# SCH_5_Li_ion_battery_charger_2022-08-25.net
KiCad netlist of a schematic drawn in EasyEDA
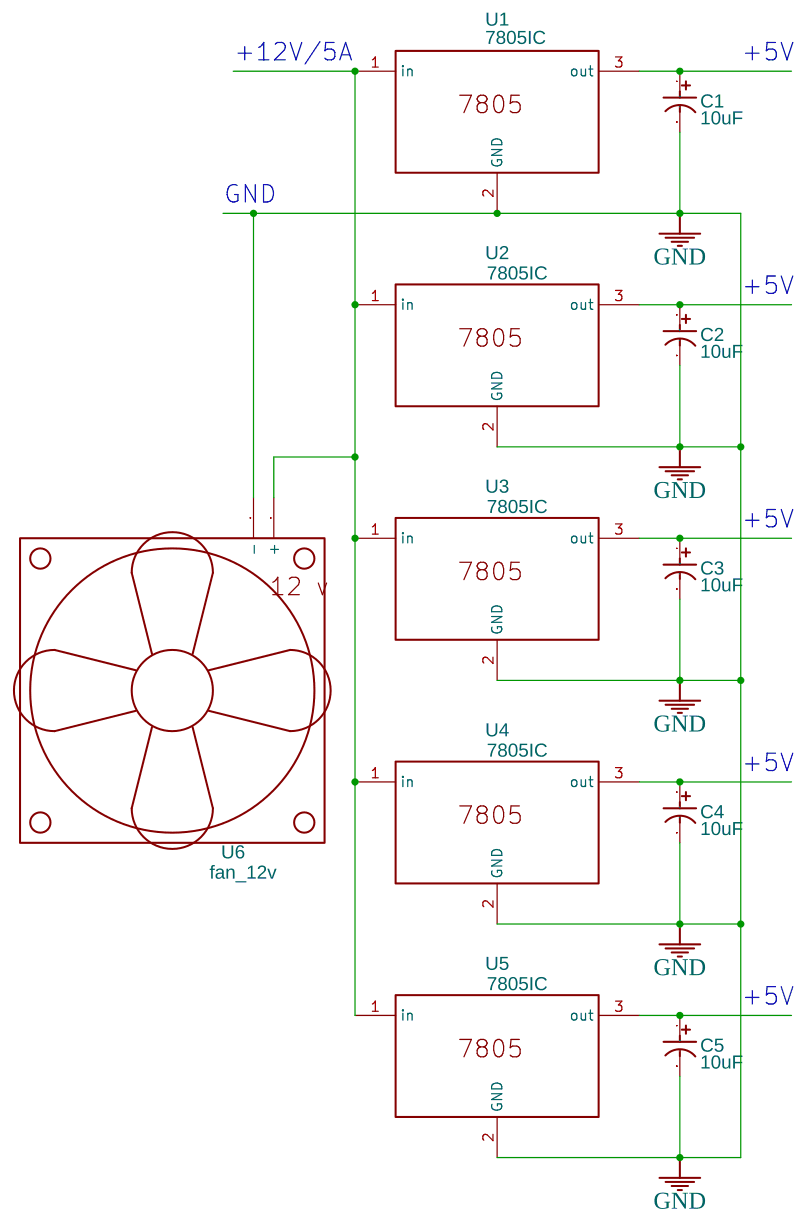
[diagram p0: 12v to 5v]
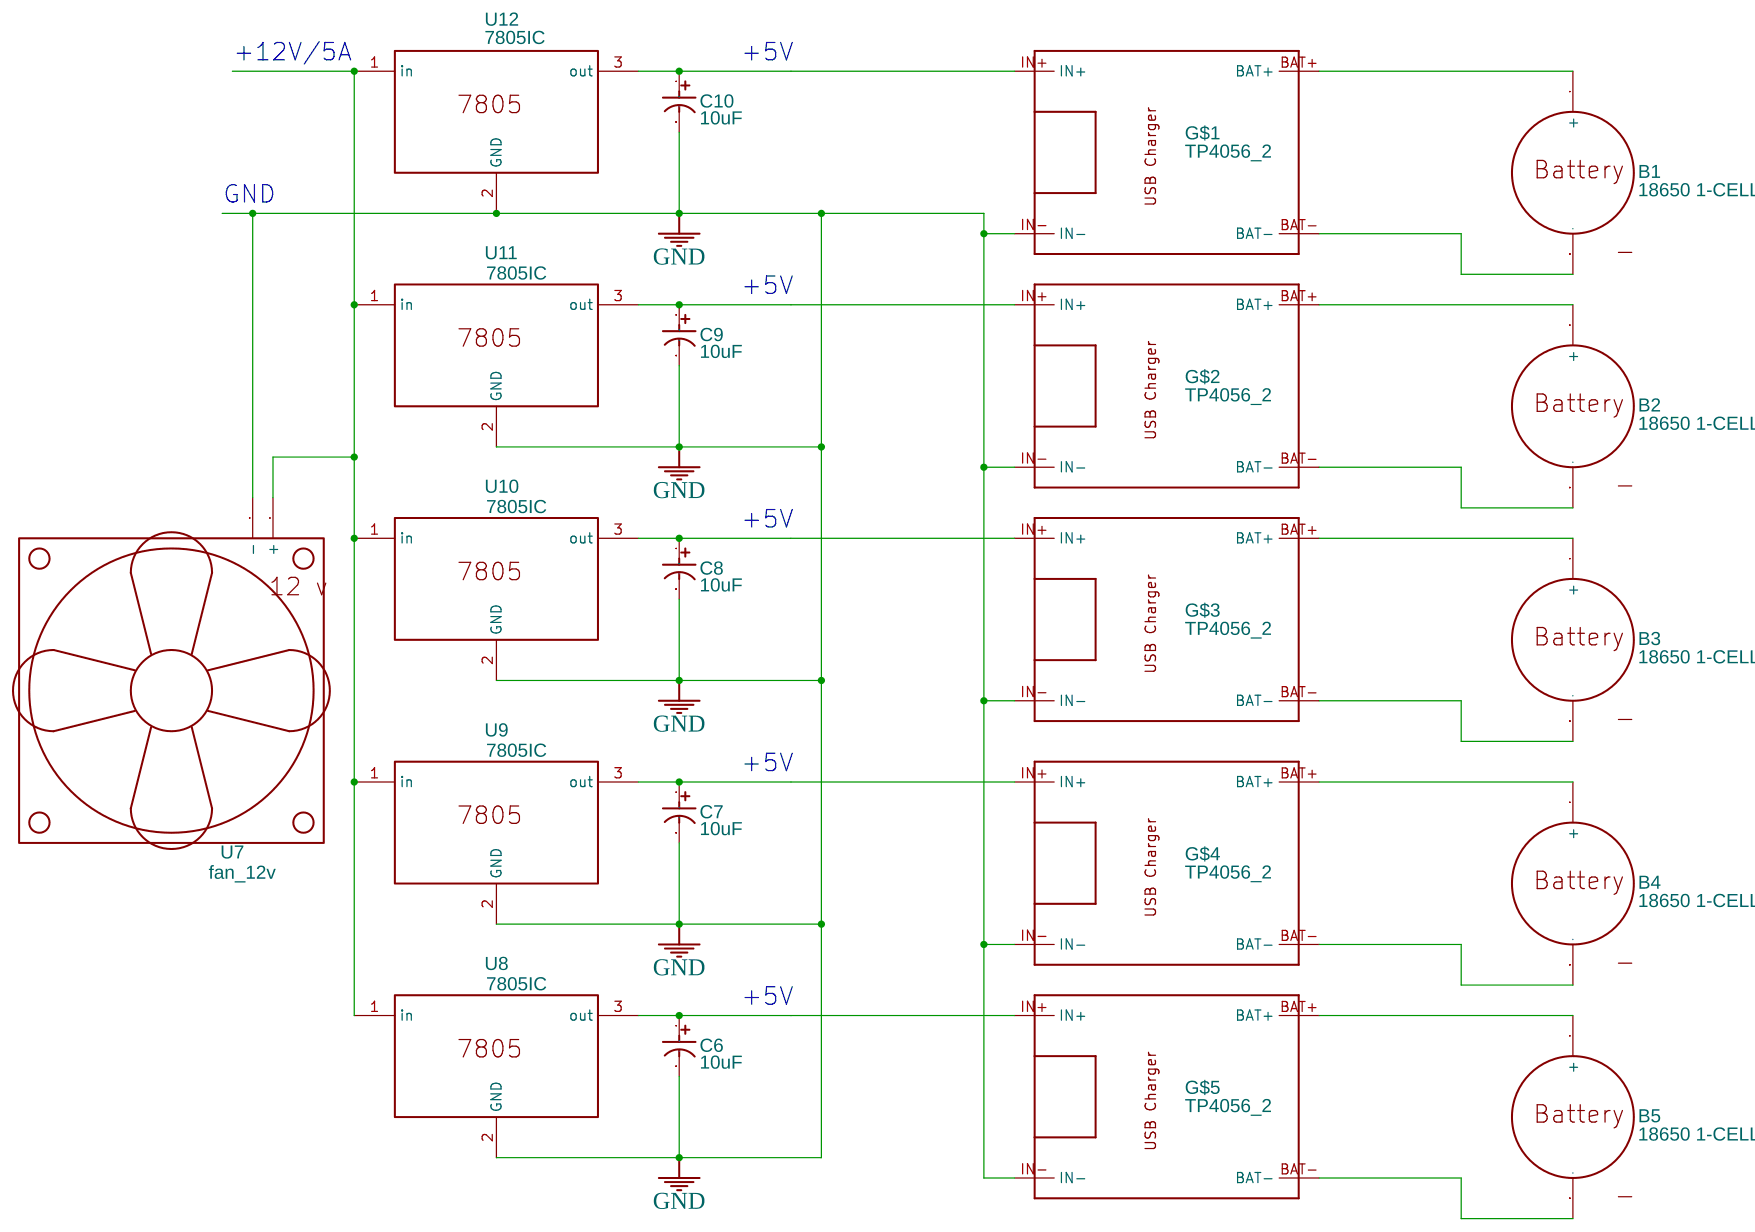
[diagram p1: connection with TP4056]
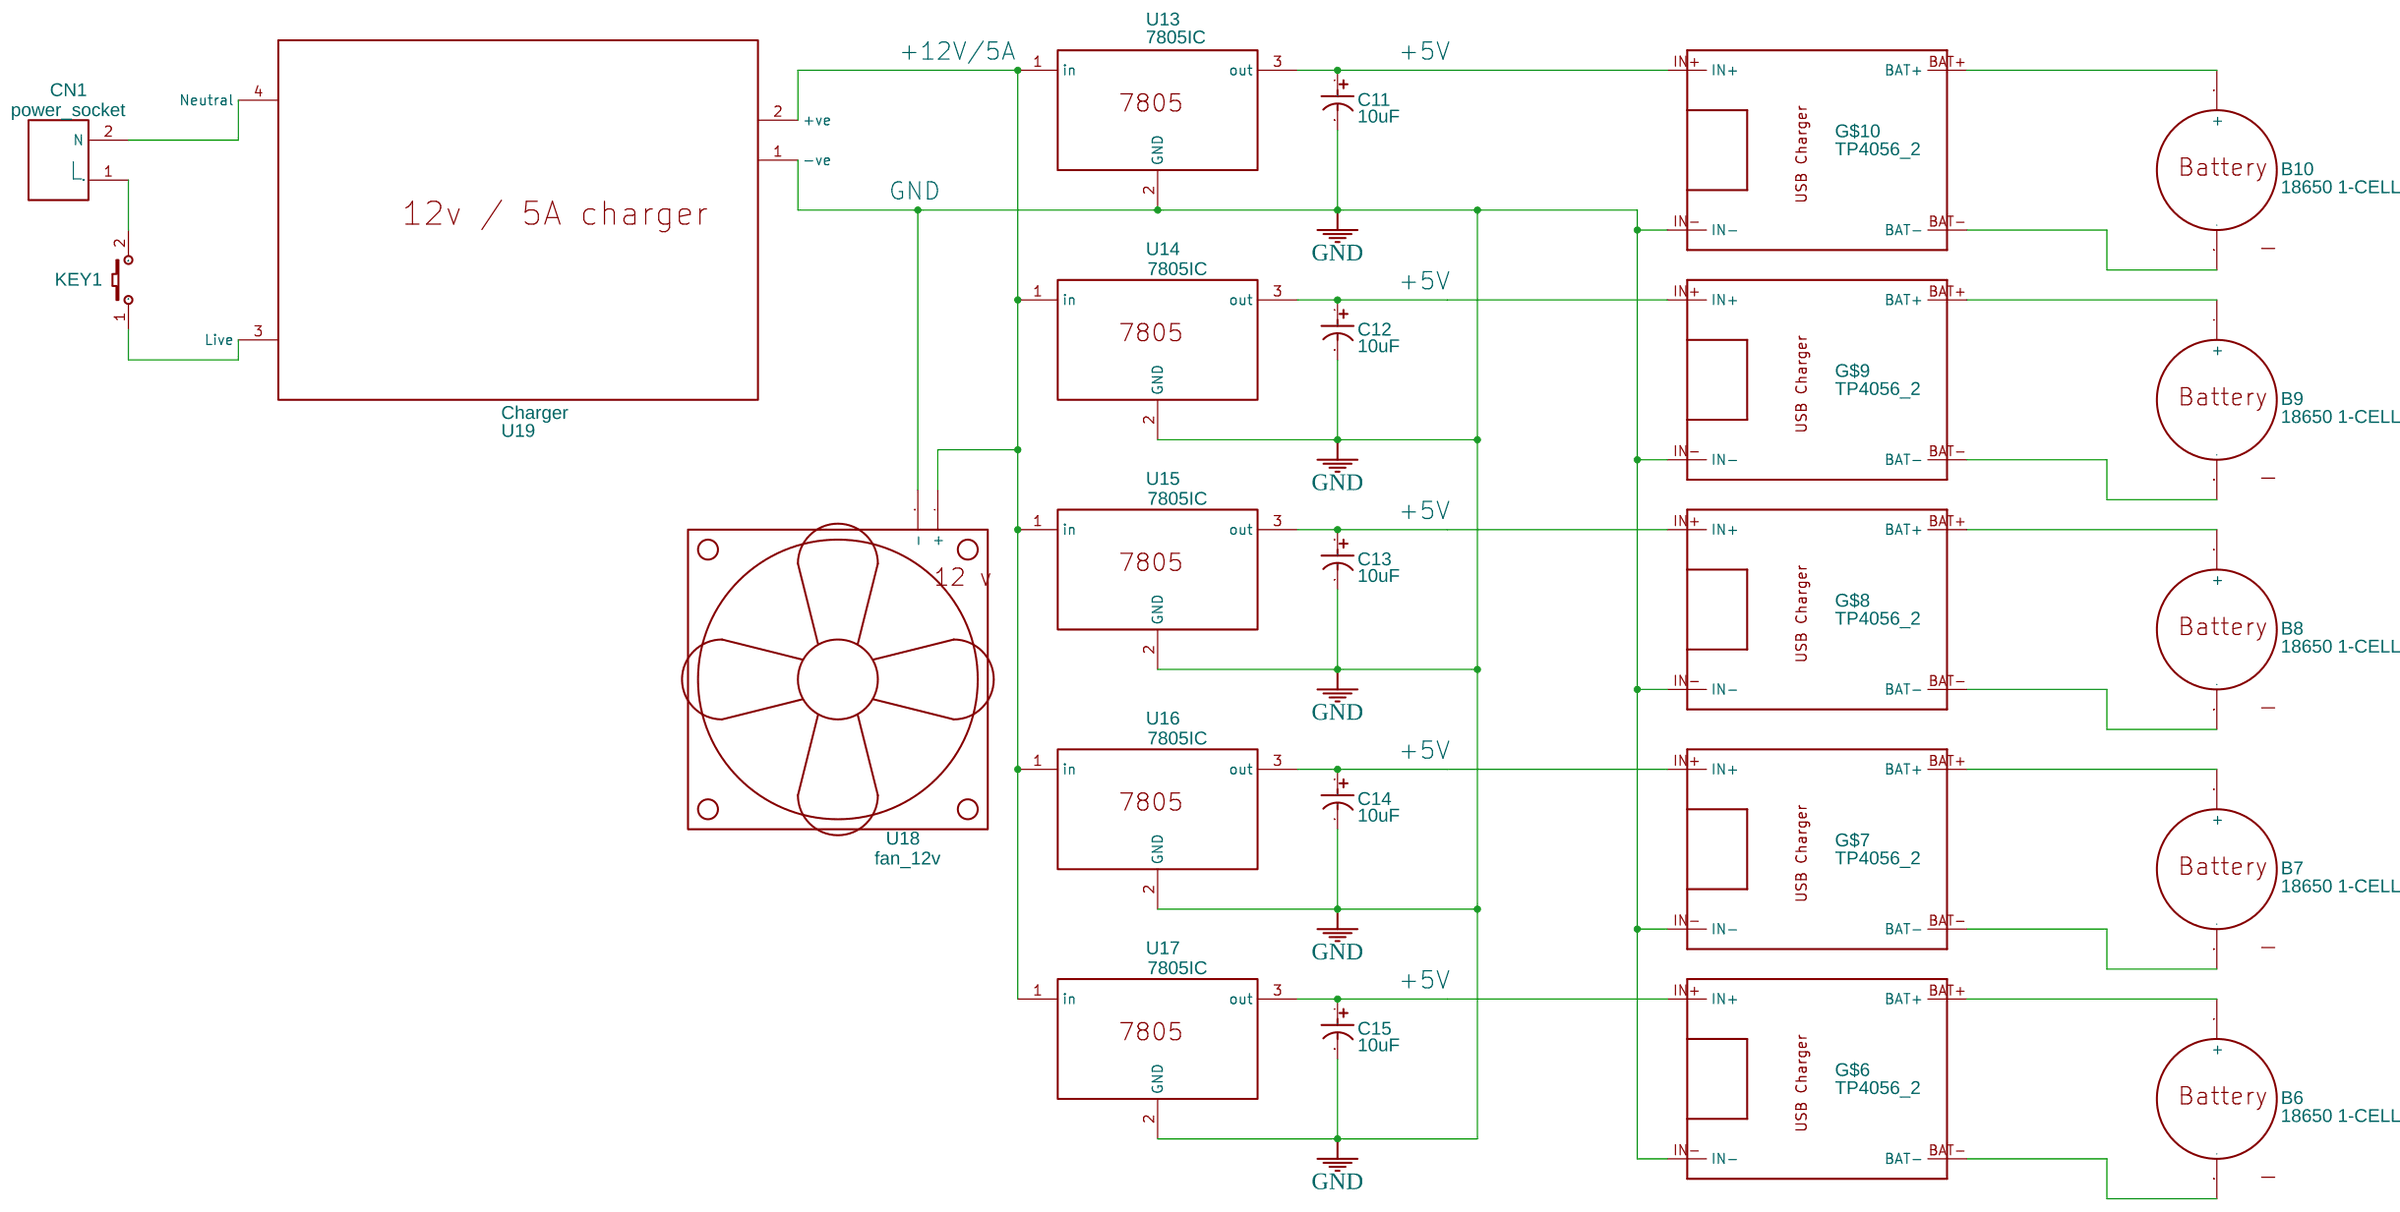
[diagram p2: Complete Circuit Diagram]

(export (version "E")
  (design (tool "Eeschema 10.0.6"))
  (components
    (comp (ref "C1")
      (value "10uF")
      (fields
        (field (name "BOM_Manufacturer Part") "electrolytic capacitor10UF50V")
        (field (name "BOM_Supplier Part") "C32856")
      )
      (libsource (lib "") (part "CAPACITOR1000UF16V"))
    )
    (comp (ref "C2")
      (value "10uF")
      (fields
        (field (name "BOM_Manufacturer Part") "electrolytic capacitor10UF50V")
        (field (name "BOM_Supplier Part") "C32856")
      )
      (libsource (lib "") (part "CAPACITOR1000UF16V"))
    )
    (comp (ref "C3")
      (value "10uF")
      (fields
        (field (name "BOM_Manufacturer Part") "electrolytic capacitor10UF50V")
        (field (name "BOM_Supplier Part") "C32856")
      )
      (libsource (lib "") (part "CAPACITOR1000UF16V"))
    )
    (comp (ref "C4")
      (value "10uF")
      (fields
        (field (name "BOM_Manufacturer Part") "electrolytic capacitor10UF50V")
        (field (name "BOM_Supplier Part") "C32856")
      )
      (libsource (lib "") (part "CAPACITOR1000UF16V"))
    )
    (comp (ref "C5")
      (value "10uF")
      (fields
        (field (name "BOM_Manufacturer Part") "electrolytic capacitor10UF50V")
        (field (name "BOM_Supplier Part") "C32856")
      )
      (libsource (lib "") (part "CAPACITOR1000UF16V"))
    )
    (comp (ref "U1") (value "7805IC") (libsource (lib "") (part "7805IC")))
    (comp (ref "U2") (value "7805IC") (libsource (lib "") (part "7805IC")))
    (comp (ref "U3") (value "7805IC") (libsource (lib "") (part "7805IC")))
    (comp (ref "U4") (value "7805IC") (libsource (lib "") (part "7805IC")))
    (comp (ref "U5") (value "7805IC") (libsource (lib "") (part "7805IC")))
    (comp (ref "U6") (value "fan_12v") (libsource (lib "") (part "fan_12v")))
    (comp (ref "B1")
      (value "18650 1-CELL HOLDER")
      (fields (field (name "BOM_Manufacturer Part") "Battery_holder_18650"))
      (libsource (lib "") (part "18650 1-CELL HOLDER"))
    )
    (comp (ref "B2")
      (value "18650 1-CELL HOLDER")
      (fields (field (name "BOM_Manufacturer Part") "Battery_holder_18650"))
      (libsource (lib "") (part "18650 1-CELL HOLDER"))
    )
    (comp (ref "B3")
      (value "18650 1-CELL HOLDER")
      (fields (field (name "BOM_Manufacturer Part") "Battery_holder_18650"))
      (libsource (lib "") (part "18650 1-CELL HOLDER"))
    )
    (comp (ref "B4")
      (value "18650 1-CELL HOLDER")
      (fields (field (name "BOM_Manufacturer Part") "Battery_holder_18650"))
      (libsource (lib "") (part "18650 1-CELL HOLDER"))
    )
    (comp (ref "B5")
      (value "18650 1-CELL HOLDER")
      (fields (field (name "BOM_Manufacturer Part") "Battery_holder_18650"))
      (libsource (lib "") (part "18650 1-CELL HOLDER"))
    )
    (comp (ref "C6")
      (value "10uF")
      (fields
        (field (name "BOM_Manufacturer Part") "electrolytic capacitor10UF50V")
        (field (name "BOM_Supplier Part") "C32856")
      )
      (libsource (lib "") (part "CAPACITOR1000UF16V"))
    )
    (comp (ref "C7")
      (value "10uF")
      (fields
        (field (name "BOM_Manufacturer Part") "electrolytic capacitor10UF50V")
        (field (name "BOM_Supplier Part") "C32856")
      )
      (libsource (lib "") (part "CAPACITOR1000UF16V"))
    )
    (comp (ref "C8")
      (value "10uF")
      (fields
        (field (name "BOM_Manufacturer Part") "electrolytic capacitor10UF50V")
        (field (name "BOM_Supplier Part") "C32856")
      )
      (libsource (lib "") (part "CAPACITOR1000UF16V"))
    )
    (comp (ref "C9")
      (value "10uF")
      (fields
        (field (name "BOM_Manufacturer Part") "electrolytic capacitor10UF50V")
        (field (name "BOM_Supplier Part") "C32856")
      )
      (libsource (lib "") (part "CAPACITOR1000UF16V"))
    )
    (comp (ref "C10")
      (value "10uF")
      (fields
        (field (name "BOM_Manufacturer Part") "electrolytic capacitor10UF50V")
        (field (name "BOM_Supplier Part") "C32856")
      )
      (libsource (lib "") (part "CAPACITOR1000UF16V"))
    )
    (comp (ref "G$1") (value "TP4056_2") (libsource (lib "") (part "TP4056_2_1")))
    (comp (ref "G$2") (value "TP4056_2") (libsource (lib "") (part "TP4056_2")))
    (comp (ref "G$3") (value "TP4056_2") (libsource (lib "") (part "TP4056_2")))
    (comp (ref "G$4") (value "TP4056_2") (libsource (lib "") (part "TP4056_2")))
    (comp (ref "G$5") (value "TP4056_2") (libsource (lib "") (part "TP4056_2")))
    (comp (ref "U7") (value "fan_12v") (libsource (lib "") (part "fan_12v")))
    (comp (ref "U8") (value "7805IC") (libsource (lib "") (part "7805IC")))
    (comp (ref "U9") (value "7805IC") (libsource (lib "") (part "7805IC")))
    (comp (ref "U10") (value "7805IC") (libsource (lib "") (part "7805IC")))
    (comp (ref "U11") (value "7805IC") (libsource (lib "") (part "7805IC")))
    (comp (ref "U12") (value "7805IC") (libsource (lib "") (part "7805IC")))
    (comp (ref "B6")
      (value "18650 1-CELL HOLDER")
      (fields (field (name "BOM_Manufacturer Part") "Battery_holder_18650"))
      (libsource (lib "") (part "18650 1-CELL HOLDER"))
    )
    (comp (ref "B7")
      (value "18650 1-CELL HOLDER")
      (fields (field (name "BOM_Manufacturer Part") "Battery_holder_18650"))
      (libsource (lib "") (part "18650 1-CELL HOLDER"))
    )
    (comp (ref "B8")
      (value "18650 1-CELL HOLDER")
      (fields (field (name "BOM_Manufacturer Part") "Battery_holder_18650"))
      (libsource (lib "") (part "18650 1-CELL HOLDER"))
    )
    (comp (ref "B9")
      (value "18650 1-CELL HOLDER")
      (fields (field (name "BOM_Manufacturer Part") "Battery_holder_18650"))
      (libsource (lib "") (part "18650 1-CELL HOLDER"))
    )
    (comp (ref "B10")
      (value "18650 1-CELL HOLDER")
      (fields (field (name "BOM_Manufacturer Part") "Battery_holder_18650"))
      (libsource (lib "") (part "18650 1-CELL HOLDER"))
    )
    (comp (ref "C11")
      (value "10uF")
      (fields
        (field (name "BOM_Manufacturer Part") "electrolytic capacitor10UF50V")
        (field (name "BOM_Supplier Part") "C32856")
      )
      (libsource (lib "") (part "CAPACITOR1000UF16V"))
    )
    (comp (ref "C12")
      (value "10uF")
      (fields
        (field (name "BOM_Manufacturer Part") "electrolytic capacitor10UF50V")
        (field (name "BOM_Supplier Part") "C32856")
      )
      (libsource (lib "") (part "CAPACITOR1000UF16V"))
    )
    (comp (ref "C13")
      (value "10uF")
      (fields
        (field (name "BOM_Manufacturer Part") "electrolytic capacitor10UF50V")
        (field (name "BOM_Supplier Part") "C32856")
      )
      (libsource (lib "") (part "CAPACITOR1000UF16V"))
    )
    (comp (ref "C14")
      (value "10uF")
      (fields
        (field (name "BOM_Manufacturer Part") "electrolytic capacitor10UF50V")
        (field (name "BOM_Supplier Part") "C32856")
      )
      (libsource (lib "") (part "CAPACITOR1000UF16V"))
    )
    (comp (ref "C15")
      (value "10uF")
      (fields
        (field (name "BOM_Manufacturer Part") "electrolytic capacitor10UF50V")
        (field (name "BOM_Supplier Part") "C32856")
      )
      (libsource (lib "") (part "CAPACITOR1000UF16V"))
    )
    (comp (ref "CN1")
      (value "power_socket")
      (fields
        (field (name "BOM_Manufacturer Part") "socket.blue5566-2Aneedle")
        (field (name "BOM_Supplier Part") "C62133")
      )
      (libsource (lib "") (part "power_socket"))
    )
    (comp (ref "G$6") (value "TP4056_2") (libsource (lib "") (part "TP4056_2")))
    (comp (ref "G$7") (value "TP4056_2") (libsource (lib "") (part "TP4056_2")))
    (comp (ref "G$8") (value "TP4056_2") (libsource (lib "") (part "TP4056_2")))
    (comp (ref "G$9") (value "TP4056_2") (libsource (lib "") (part "TP4056_2")))
    (comp (ref "G$10") (value "TP4056_2") (libsource (lib "") (part "TP4056_2_1")))
    (comp (ref "KEY1")
      (value "K2-3.6×6.1_SMD")
      (fields
        (field (name "BOM_Manufacturer Part") "K2-1107ST-A4SW-06")
        (field (name "BOM_Supplier Part") "C118141")
      )
      (libsource (lib "") (part "K2-3.6×6.1_SMD"))
    )
    (comp (ref "U13") (value "7805IC") (libsource (lib "") (part "7805IC")))
    (comp (ref "U14") (value "7805IC") (libsource (lib "") (part "7805IC")))
    (comp (ref "U15") (value "7805IC") (libsource (lib "") (part "7805IC")))
    (comp (ref "U16") (value "7805IC") (libsource (lib "") (part "7805IC")))
    (comp (ref "U17") (value "7805IC") (libsource (lib "") (part "7805IC")))
    (comp (ref "U18") (value "fan_12v") (libsource (lib "") (part "fan_12v")))
    (comp (ref "U19") (value "Charger") (libsource (lib "") (part "Charger")))
  )
  (nets
    (net (code "1") (name "GND") (class "Default")
      (node (ref "C1") (pin "2") (pinfunction "-_2") (pintype "input"))
      (node (ref "C10") (pin "2") (pinfunction "-_2") (pintype "input"))
      (node (ref "C11") (pin "2") (pinfunction "-_2") (pintype "input"))
      (node (ref "C12") (pin "2") (pinfunction "-_2") (pintype "input"))
      (node (ref "C13") (pin "2") (pinfunction "-_2") (pintype "input"))
      (node (ref "C14") (pin "2") (pinfunction "-_2") (pintype "input"))
      (node (ref "C15") (pin "2") (pinfunction "-_2") (pintype "input"))
      (node (ref "C2") (pin "2") (pinfunction "-_2") (pintype "input"))
      (node (ref "C3") (pin "2") (pinfunction "-_2") (pintype "input"))
      (node (ref "C4") (pin "2") (pinfunction "-_2") (pintype "input"))
      (node (ref "C5") (pin "2") (pinfunction "-_2") (pintype "input"))
      (node (ref "C6") (pin "2") (pinfunction "-_2") (pintype "input"))
      (node (ref "C7") (pin "2") (pinfunction "-_2") (pintype "input"))
      (node (ref "C8") (pin "2") (pinfunction "-_2") (pintype "input"))
      (node (ref "C9") (pin "2") (pinfunction "-_2") (pintype "input"))
      (node (ref "G$1") (pin "IN-") (pinfunction "IN-_IN-") (pintype "bidirectional"))
      (node (ref "G$10") (pin "IN-") (pinfunction "IN-_IN-") (pintype "bidirectional"))
      (node (ref "G$2") (pin "IN-") (pinfunction "IN-_IN-") (pintype "bidirectional"))
      (node (ref "G$3") (pin "IN-") (pinfunction "IN-_IN-") (pintype "bidirectional"))
      (node (ref "G$4") (pin "IN-") (pinfunction "IN-_IN-") (pintype "bidirectional"))
      (node (ref "G$5") (pin "IN-") (pinfunction "IN-_IN-") (pintype "bidirectional"))
      (node (ref "G$6") (pin "IN-") (pinfunction "IN-_IN-") (pintype "bidirectional"))
      (node (ref "G$7") (pin "IN-") (pinfunction "IN-_IN-") (pintype "bidirectional"))
      (node (ref "G$8") (pin "IN-") (pinfunction "IN-_IN-") (pintype "bidirectional"))
      (node (ref "G$9") (pin "IN-") (pinfunction "IN-_IN-") (pintype "bidirectional"))
      (node (ref "U1") (pin "2") (pinfunction "GND_2") (pintype "unspecified"))
      (node (ref "U10") (pin "2") (pinfunction "GND_2") (pintype "unspecified"))
      (node (ref "U11") (pin "2") (pinfunction "GND_2") (pintype "unspecified"))
      (node (ref "U12") (pin "2") (pinfunction "GND_2") (pintype "unspecified"))
      (node (ref "U13") (pin "2") (pinfunction "GND_2") (pintype "unspecified"))
      (node (ref "U14") (pin "2") (pinfunction "GND_2") (pintype "unspecified"))
      (node (ref "U15") (pin "2") (pinfunction "GND_2") (pintype "unspecified"))
      (node (ref "U16") (pin "2") (pinfunction "GND_2") (pintype "unspecified"))
      (node (ref "U17") (pin "2") (pinfunction "GND_2") (pintype "unspecified"))
      (node (ref "U18") (pin "2") (pinfunction "-_2") (pintype "unspecified"))
      (node (ref "U2") (pin "2") (pinfunction "GND_2") (pintype "unspecified"))
      (node (ref "U3") (pin "2") (pinfunction "GND_2") (pintype "unspecified"))
      (node (ref "U4") (pin "2") (pinfunction "GND_2") (pintype "unspecified"))
      (node (ref "U5") (pin "2") (pinfunction "GND_2") (pintype "unspecified"))
      (node (ref "U6") (pin "2") (pinfunction "-_2") (pintype "unspecified"))
      (node (ref "U7") (pin "2") (pinfunction "-_2") (pintype "unspecified"))
      (node (ref "U8") (pin "2") (pinfunction "GND_2") (pintype "unspecified"))
      (node (ref "U9") (pin "2") (pinfunction "GND_2") (pintype "unspecified"))
    )
    (net (code "2") (name "Net-(B1-+)") (class "Default")
      (node (ref "B1") (pin "1") (pinfunction "+_1") (pintype "unspecified"))
      (node (ref "G$1") (pin "BAT+") (pinfunction "BAT+_BAT+") (pintype "bidirectional"))
    )
    (net (code "3") (name "Net-(B1--)") (class "Default")
      (node (ref "B1") (pin "2") (pinfunction "-_2") (pintype "unspecified"))
      (node (ref "G$1") (pin "BAT-") (pinfunction "BAT-_BAT-") (pintype "bidirectional"))
    )
    (net (code "4") (name "Net-(B2-+)") (class "Default")
      (node (ref "B2") (pin "1") (pinfunction "+_1") (pintype "unspecified"))
      (node (ref "G$2") (pin "BAT+") (pinfunction "BAT+_BAT+") (pintype "bidirectional"))
    )
    (net (code "5") (name "Net-(B2--)") (class "Default")
      (node (ref "B2") (pin "2") (pinfunction "-_2") (pintype "unspecified"))
      (node (ref "G$2") (pin "BAT-") (pinfunction "BAT-_BAT-") (pintype "bidirectional"))
    )
    (net (code "6") (name "Net-(B3-+)") (class "Default")
      (node (ref "B3") (pin "1") (pinfunction "+_1") (pintype "unspecified"))
      (node (ref "G$3") (pin "BAT+") (pinfunction "BAT+_BAT+") (pintype "bidirectional"))
    )
    (net (code "7") (name "Net-(B3--)") (class "Default")
      (node (ref "B3") (pin "2") (pinfunction "-_2") (pintype "unspecified"))
      (node (ref "G$3") (pin "BAT-") (pinfunction "BAT-_BAT-") (pintype "bidirectional"))
    )
    (net (code "8") (name "Net-(B4-+)") (class "Default")
      (node (ref "B4") (pin "1") (pinfunction "+_1") (pintype "unspecified"))
      (node (ref "G$4") (pin "BAT+") (pinfunction "BAT+_BAT+") (pintype "bidirectional"))
    )
    (net (code "9") (name "Net-(B4--)") (class "Default")
      (node (ref "B4") (pin "2") (pinfunction "-_2") (pintype "unspecified"))
      (node (ref "G$4") (pin "BAT-") (pinfunction "BAT-_BAT-") (pintype "bidirectional"))
    )
    (net (code "10") (name "Net-(B5-+)") (class "Default")
      (node (ref "B5") (pin "1") (pinfunction "+_1") (pintype "unspecified"))
      (node (ref "G$5") (pin "BAT+") (pinfunction "BAT+_BAT+") (pintype "bidirectional"))
    )
    (net (code "11") (name "Net-(B5--)") (class "Default")
      (node (ref "B5") (pin "2") (pinfunction "-_2") (pintype "unspecified"))
      (node (ref "G$5") (pin "BAT-") (pinfunction "BAT-_BAT-") (pintype "bidirectional"))
    )
    (net (code "12") (name "Net-(B6-+)") (class "Default")
      (node (ref "B6") (pin "1") (pinfunction "+_1") (pintype "unspecified"))
      (node (ref "G$6") (pin "BAT+") (pinfunction "BAT+_BAT+") (pintype "bidirectional"))
    )
    (net (code "13") (name "Net-(B6--)") (class "Default")
      (node (ref "B6") (pin "2") (pinfunction "-_2") (pintype "unspecified"))
      (node (ref "G$6") (pin "BAT-") (pinfunction "BAT-_BAT-") (pintype "bidirectional"))
    )
    (net (code "14") (name "Net-(B7-+)") (class "Default")
      (node (ref "B7") (pin "1") (pinfunction "+_1") (pintype "unspecified"))
      (node (ref "G$7") (pin "BAT+") (pinfunction "BAT+_BAT+") (pintype "bidirectional"))
    )
    (net (code "15") (name "Net-(B7--)") (class "Default")
      (node (ref "B7") (pin "2") (pinfunction "-_2") (pintype "unspecified"))
      (node (ref "G$7") (pin "BAT-") (pinfunction "BAT-_BAT-") (pintype "bidirectional"))
    )
    (net (code "16") (name "Net-(B8-+)") (class "Default")
      (node (ref "B8") (pin "1") (pinfunction "+_1") (pintype "unspecified"))
      (node (ref "G$8") (pin "BAT+") (pinfunction "BAT+_BAT+") (pintype "bidirectional"))
    )
    (net (code "17") (name "Net-(B8--)") (class "Default")
      (node (ref "B8") (pin "2") (pinfunction "-_2") (pintype "unspecified"))
      (node (ref "G$8") (pin "BAT-") (pinfunction "BAT-_BAT-") (pintype "bidirectional"))
    )
    (net (code "18") (name "Net-(B9-+)") (class "Default")
      (node (ref "B9") (pin "1") (pinfunction "+_1") (pintype "unspecified"))
      (node (ref "G$9") (pin "BAT+") (pinfunction "BAT+_BAT+") (pintype "bidirectional"))
    )
    (net (code "19") (name "Net-(B9--)") (class "Default")
      (node (ref "B9") (pin "2") (pinfunction "-_2") (pintype "unspecified"))
      (node (ref "G$9") (pin "BAT-") (pinfunction "BAT-_BAT-") (pintype "bidirectional"))
    )
    (net (code "20") (name "Net-(B10-+)") (class "Default")
      (node (ref "B10") (pin "1") (pinfunction "+_1") (pintype "unspecified"))
      (node (ref "G$10") (pin "BAT+") (pinfunction "BAT+_BAT+") (pintype "bidirectional"))
    )
    (net (code "21") (name "Net-(B10--)") (class "Default")
      (node (ref "B10") (pin "2") (pinfunction "-_2") (pintype "unspecified"))
      (node (ref "G$10") (pin "BAT-") (pinfunction "BAT-_BAT-") (pintype "bidirectional"))
    )
    (net (code "22") (name "Net-(C1-+)") (class "Default")
      (node (ref "C1") (pin "1") (pinfunction "+_1") (pintype "input"))
      (node (ref "U1") (pin "3") (pinfunction "out_3") (pintype "unspecified"))
    )
    (net (code "23") (name "Net-(C2-+)") (class "Default")
      (node (ref "C2") (pin "1") (pinfunction "+_1") (pintype "input"))
      (node (ref "U2") (pin "3") (pinfunction "out_3") (pintype "unspecified"))
    )
    (net (code "24") (name "Net-(C3-+)") (class "Default")
      (node (ref "C3") (pin "1") (pinfunction "+_1") (pintype "input"))
      (node (ref "U3") (pin "3") (pinfunction "out_3") (pintype "unspecified"))
    )
    (net (code "25") (name "Net-(C4-+)") (class "Default")
      (node (ref "C4") (pin "1") (pinfunction "+_1") (pintype "input"))
      (node (ref "U4") (pin "3") (pinfunction "out_3") (pintype "unspecified"))
    )
    (net (code "26") (name "Net-(C5-+)") (class "Default")
      (node (ref "C5") (pin "1") (pinfunction "+_1") (pintype "input"))
      (node (ref "U5") (pin "3") (pinfunction "out_3") (pintype "unspecified"))
    )
    (net (code "27") (name "Net-(C6-+)") (class "Default")
      (node (ref "C6") (pin "1") (pinfunction "+_1") (pintype "input"))
      (node (ref "G$5") (pin "IN+") (pinfunction "IN+_IN+") (pintype "bidirectional"))
      (node (ref "U8") (pin "3") (pinfunction "out_3") (pintype "unspecified"))
    )
    (net (code "28") (name "Net-(C7-+)") (class "Default")
      (node (ref "C7") (pin "1") (pinfunction "+_1") (pintype "input"))
      (node (ref "G$4") (pin "IN+") (pinfunction "IN+_IN+") (pintype "bidirectional"))
      (node (ref "U9") (pin "3") (pinfunction "out_3") (pintype "unspecified"))
    )
    (net (code "29") (name "Net-(C8-+)") (class "Default")
      (node (ref "C8") (pin "1") (pinfunction "+_1") (pintype "input"))
      (node (ref "G$3") (pin "IN+") (pinfunction "IN+_IN+") (pintype "bidirectional"))
      (node (ref "U10") (pin "3") (pinfunction "out_3") (pintype "unspecified"))
    )
    (net (code "30") (name "Net-(C9-+)") (class "Default")
      (node (ref "C9") (pin "1") (pinfunction "+_1") (pintype "input"))
      (node (ref "G$2") (pin "IN+") (pinfunction "IN+_IN+") (pintype "bidirectional"))
      (node (ref "U11") (pin "3") (pinfunction "out_3") (pintype "unspecified"))
    )
    (net (code "31") (name "Net-(C10-+)") (class "Default")
      (node (ref "C10") (pin "1") (pinfunction "+_1") (pintype "input"))
      (node (ref "G$1") (pin "IN+") (pinfunction "IN+_IN+") (pintype "bidirectional"))
      (node (ref "U12") (pin "3") (pinfunction "out_3") (pintype "unspecified"))
    )
    (net (code "32") (name "Net-(C11-+)") (class "Default")
      (node (ref "C11") (pin "1") (pinfunction "+_1") (pintype "input"))
      (node (ref "G$10") (pin "IN+") (pinfunction "IN+_IN+") (pintype "bidirectional"))
      (node (ref "U13") (pin "3") (pinfunction "out_3") (pintype "unspecified"))
    )
    (net (code "33") (name "Net-(C12-+)") (class "Default")
      (node (ref "C12") (pin "1") (pinfunction "+_1") (pintype "input"))
      (node (ref "G$9") (pin "IN+") (pinfunction "IN+_IN+") (pintype "bidirectional"))
      (node (ref "U14") (pin "3") (pinfunction "out_3") (pintype "unspecified"))
    )
    (net (code "34") (name "Net-(C13-+)") (class "Default")
      (node (ref "C13") (pin "1") (pinfunction "+_1") (pintype "input"))
      (node (ref "G$8") (pin "IN+") (pinfunction "IN+_IN+") (pintype "bidirectional"))
      (node (ref "U15") (pin "3") (pinfunction "out_3") (pintype "unspecified"))
    )
    (net (code "35") (name "Net-(C14-+)") (class "Default")
      (node (ref "C14") (pin "1") (pinfunction "+_1") (pintype "input"))
      (node (ref "G$7") (pin "IN+") (pinfunction "IN+_IN+") (pintype "bidirectional"))
      (node (ref "U16") (pin "3") (pinfunction "out_3") (pintype "unspecified"))
    )
    (net (code "36") (name "Net-(C15-+)") (class "Default")
      (node (ref "C15") (pin "1") (pinfunction "+_1") (pintype "input"))
      (node (ref "G$6") (pin "IN+") (pinfunction "IN+_IN+") (pintype "bidirectional"))
      (node (ref "U17") (pin "3") (pinfunction "out_3") (pintype "unspecified"))
    )
    (net (code "37") (name "Net-(CN1-Line)") (class "Default")
      (node (ref "CN1") (pin "1") (pinfunction "Line_1") (pintype "unspecified"))
      (node (ref "KEY1") (pin "2") (pinfunction "2_2") (pintype "unspecified"))
    )
    (net (code "38") (name "Net-(U1-in)") (class "Default")
      (node (ref "U1") (pin "1") (pinfunction "in_1") (pintype "unspecified"))
      (node (ref "U2") (pin "1") (pinfunction "in_1") (pintype "unspecified"))
      (node (ref "U3") (pin "1") (pinfunction "in_1") (pintype "unspecified"))
      (node (ref "U4") (pin "1") (pinfunction "in_1") (pintype "unspecified"))
      (node (ref "U5") (pin "1") (pinfunction "in_1") (pintype "unspecified"))
      (node (ref "U6") (pin "1") (pinfunction "+_1") (pintype "unspecified"))
    )
    (net (code "39") (name "Net-(U10-in)") (class "Default")
      (node (ref "U10") (pin "1") (pinfunction "in_1") (pintype "unspecified"))
      (node (ref "U11") (pin "1") (pinfunction "in_1") (pintype "unspecified"))
      (node (ref "U12") (pin "1") (pinfunction "in_1") (pintype "unspecified"))
      (node (ref "U7") (pin "1") (pinfunction "+_1") (pintype "unspecified"))
      (node (ref "U8") (pin "1") (pinfunction "in_1") (pintype "unspecified"))
      (node (ref "U9") (pin "1") (pinfunction "in_1") (pintype "unspecified"))
    )
    (net (code "40") (name "Net-(U13-in)") (class "Default")
      (node (ref "U13") (pin "1") (pinfunction "in_1") (pintype "unspecified"))
      (node (ref "U14") (pin "1") (pinfunction "in_1") (pintype "unspecified"))
      (node (ref "U15") (pin "1") (pinfunction "in_1") (pintype "unspecified"))
      (node (ref "U16") (pin "1") (pinfunction "in_1") (pintype "unspecified"))
      (node (ref "U17") (pin "1") (pinfunction "in_1") (pintype "unspecified"))
      (node (ref "U18") (pin "1") (pinfunction "+_1") (pintype "unspecified"))
    )
    (net (code "41") (name "unconnected-(CN1-N-Pad2)") (class "Default")
      (node (ref "CN1") (pin "2") (pinfunction "N_2") (pintype "unspecified"))
    )
    (net (code "42") (name "unconnected-(KEY1-Pad1)") (class "Default")
      (node (ref "KEY1") (pin "1") (pinfunction "1_1") (pintype "unspecified"))
    )
    (net (code "43") (name "unconnected-(U19-+ve-Pad2)") (class "Default")
      (node (ref "U19") (pin "2") (pinfunction "+ve_2") (pintype "unspecified"))
    )
    (net (code "44") (name "unconnected-(U19--ve-Pad1)") (class "Default")
      (node (ref "U19") (pin "1") (pinfunction "-ve_1") (pintype "unspecified"))
    )
    (net (code "45") (name "unconnected-(U19-Live-Pad3)") (class "Default")
      (node (ref "U19") (pin "3") (pinfunction "Live_3") (pintype "unspecified"))
    )
    (net (code "46") (name "unconnected-(U19-Neutral-Pad4)") (class "Default")
      (node (ref "U19") (pin "4") (pinfunction "Neutral_4") (pintype "unspecified"))
    )
  )
)
